# ENGI301Project2.net
KiCad netlist of a schematic drawn in EAGLE
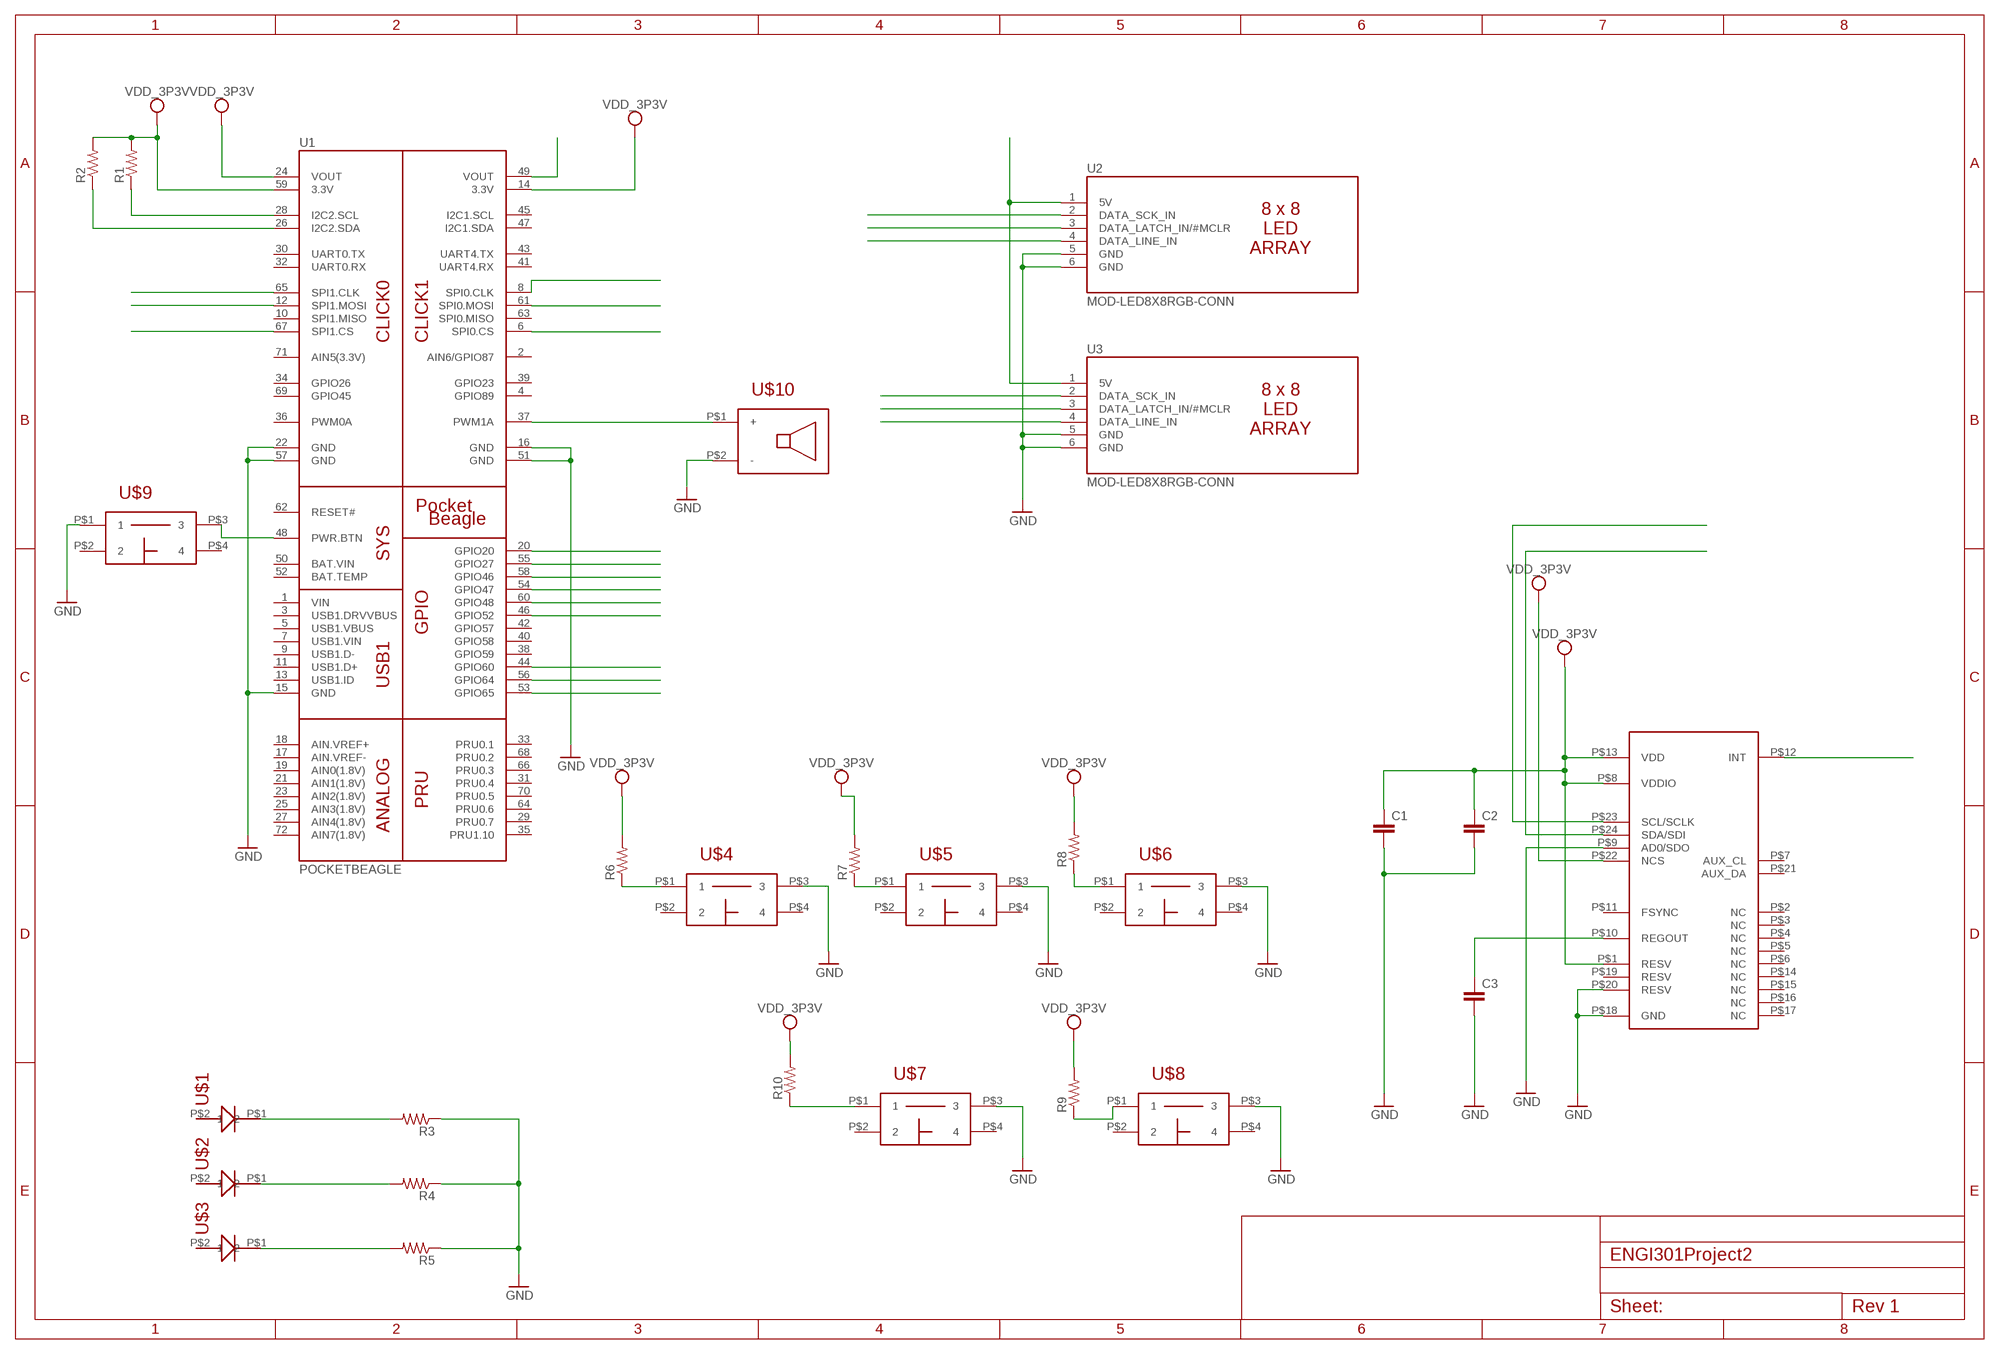
[diagram p0: schematic, sheet 1]

(export (version "E")
  (design (tool "Eeschema 10.0.6"))
  (components
    (comp (ref "C1")
      (value "C_C0603")
      (footprint "eagle-import:C0603")
      (libsource (lib "eagle-import") (part "C_C0603"))
    )
    (comp (ref "C2")
      (value "C_C0603")
      (footprint "eagle-import:C0603")
      (libsource (lib "eagle-import") (part "C_C0603"))
    )
    (comp (ref "C3")
      (value "C_C0603")
      (footprint "eagle-import:C0603")
      (libsource (lib "eagle-import") (part "C_C0603"))
    )
    (comp (ref "R1")
      (value "R_R0603")
      (footprint "eagle-import:R0603")
      (libsource (lib "eagle-import") (part "R_R0603"))
    )
    (comp (ref "R2")
      (value "R_R0603")
      (footprint "eagle-import:R0603")
      (libsource (lib "eagle-import") (part "R_R0603"))
    )
    (comp (ref "R3")
      (value "R_R0603")
      (footprint "eagle-import:R0603")
      (libsource (lib "eagle-import") (part "R_R0603"))
    )
    (comp (ref "R4")
      (value "R_R0603")
      (footprint "eagle-import:R0603")
      (libsource (lib "eagle-import") (part "R_R0603"))
    )
    (comp (ref "R5")
      (value "R_R0603")
      (footprint "eagle-import:R0603")
      (libsource (lib "eagle-import") (part "R_R0603"))
    )
    (comp (ref "R6")
      (value "R_R0603")
      (footprint "eagle-import:R0603")
      (libsource (lib "eagle-import") (part "R_R0603"))
    )
    (comp (ref "R7")
      (value "R_R0603")
      (footprint "eagle-import:R0603")
      (libsource (lib "eagle-import") (part "R_R0603"))
    )
    (comp (ref "R8")
      (value "R_R0603")
      (footprint "eagle-import:R0603")
      (libsource (lib "eagle-import") (part "R_R0603"))
    )
    (comp (ref "R9")
      (value "R_R0603")
      (footprint "eagle-import:R0603")
      (libsource (lib "eagle-import") (part "R_R0603"))
    )
    (comp (ref "R10")
      (value "R_R0603")
      (footprint "eagle-import:R0603")
      (libsource (lib "eagle-import") (part "R_R0603"))
    )
    (comp (ref "U$1")
      (value "LED")
      (footprint "eagle-import:LED")
      (libsource (lib "eagle-import") (part "LED"))
    )
    (comp (ref "U$2")
      (value "LED")
      (footprint "eagle-import:LED")
      (libsource (lib "eagle-import") (part "LED"))
    )
    (comp (ref "U$3")
      (value "LED")
      (footprint "eagle-import:LED")
      (libsource (lib "eagle-import") (part "LED"))
    )
    (comp (ref "U$4")
      (value "BUTTON")
      (footprint "eagle-import:BUTTON")
      (libsource (lib "eagle-import") (part "BUTTON"))
    )
    (comp (ref "U$5")
      (value "BUTTON")
      (footprint "eagle-import:BUTTON")
      (libsource (lib "eagle-import") (part "BUTTON"))
    )
    (comp (ref "U$6")
      (value "BUTTON")
      (footprint "eagle-import:BUTTON")
      (libsource (lib "eagle-import") (part "BUTTON"))
    )
    (comp (ref "U$7")
      (value "BUTTON")
      (footprint "eagle-import:BUTTON")
      (libsource (lib "eagle-import") (part "BUTTON"))
    )
    (comp (ref "U$8")
      (value "BUTTON")
      (footprint "eagle-import:BUTTON")
      (libsource (lib "eagle-import") (part "BUTTON"))
    )
    (comp (ref "U$9")
      (value "BUTTON")
      (footprint "eagle-import:BUTTON")
      (libsource (lib "eagle-import") (part "BUTTON"))
    )
    (comp (ref "U$10")
      (value "BUZZER")
      (footprint "eagle-import:BUZZER")
      (libsource (lib "eagle-import") (part "BUZZER"))
    )
    (comp (ref "U1")
      (value "POCKETBEAGLE")
      (footprint "eagle-import:POCKETBEAGLE")
      (libsource (lib "eagle-import") (part "POCKETBEAGLE"))
    )
    (comp (ref "U2")
      (value "MOD-LED8X8RGB-CONN")
      (footprint "eagle-import:FE06W")
      (libsource (lib "eagle-import") (part "MOD-LED8X8RGB-CONN"))
    )
    (comp (ref "U3")
      (value "MOD-LED8X8RGB-CONN")
      (footprint "eagle-import:FE06W")
      (libsource (lib "eagle-import") (part "MOD-LED8X8RGB-CONN"))
    )
    (comp (ref "U6")
      (value "MPU-9250")
      (footprint "eagle-import:QFN3")
      (libsource (lib "eagle-import") (part "MPU-9250"))
    )
  )
  (nets
    (net (code "1") (name "GND") (class "Default")
      (node (ref "C1") (pin "2") (pinfunction "2_2") (pintype "passive"))
      (node (ref "C2") (pin "2") (pinfunction "2_2") (pintype "passive"))
      (node (ref "C3") (pin "2") (pinfunction "2_2") (pintype "passive"))
      (node (ref "R3") (pin "1") (pinfunction "1_1") (pintype "passive"))
      (node (ref "R4") (pin "1") (pinfunction "1_1") (pintype "passive"))
      (node (ref "R5") (pin "1") (pinfunction "1_1") (pintype "passive"))
      (node (ref "U$10") (pin "P$2") (pinfunction "-_P$2") (pintype "bidirectional"))
      (node (ref "U$4") (pin "P$3") (pinfunction "3_P$3") (pintype "bidirectional"))
      (node (ref "U$5") (pin "P$3") (pinfunction "3_P$3") (pintype "bidirectional"))
      (node (ref "U$6") (pin "P$3") (pinfunction "3_P$3") (pintype "bidirectional"))
      (node (ref "U$7") (pin "P$3") (pinfunction "3_P$3") (pintype "bidirectional"))
      (node (ref "U$8") (pin "P$3") (pinfunction "3_P$3") (pintype "bidirectional"))
      (node (ref "U$9") (pin "P$1") (pinfunction "1_P$1") (pintype "bidirectional"))
      (node (ref "U1") (pin "15") (pinfunction "GND_15") (pintype "bidirectional"))
      (node (ref "U1") (pin "16") (pinfunction "GND_16") (pintype "bidirectional"))
      (node (ref "U1") (pin "22") (pinfunction "GND_22") (pintype "bidirectional"))
      (node (ref "U1") (pin "51") (pinfunction "GND_51") (pintype "bidirectional"))
      (node (ref "U1") (pin "57") (pinfunction "GND_57") (pintype "bidirectional"))
      (node (ref "U2") (pin "5") (pinfunction "GND_5") (pintype "bidirectional"))
      (node (ref "U2") (pin "6") (pinfunction "GND_6") (pintype "bidirectional"))
      (node (ref "U3") (pin "5") (pinfunction "GND_5") (pintype "bidirectional"))
      (node (ref "U3") (pin "6") (pinfunction "GND_6") (pintype "bidirectional"))
      (node (ref "U6") (pin "P$18") (pinfunction "GND_P$18") (pintype "bidirectional"))
      (node (ref "U6") (pin "P$20") (pinfunction "RESV_P$20") (pintype "bidirectional"))
      (node (ref "U6") (pin "P$9") (pinfunction "AD0/SDO_P$9") (pintype "bidirectional"))
    )
    (net (code "2") (name "Net-(U$1-1)") (class "Default")
      (node (ref "R3") (pin "2") (pinfunction "2_2") (pintype "passive"))
      (node (ref "U$1") (pin "P$1") (pinfunction "1_P$1") (pintype "bidirectional"))
    )
    (net (code "3") (name "Net-(U$2-1)") (class "Default")
      (node (ref "R4") (pin "2") (pinfunction "2_2") (pintype "passive"))
      (node (ref "U$2") (pin "P$1") (pinfunction "1_P$1") (pintype "bidirectional"))
    )
    (net (code "4") (name "Net-(U$3-1)") (class "Default")
      (node (ref "R5") (pin "2") (pinfunction "2_2") (pintype "passive"))
      (node (ref "U$3") (pin "P$1") (pinfunction "1_P$1") (pintype "bidirectional"))
    )
    (net (code "5") (name "Net-(U$4-1)") (class "Default")
      (node (ref "R6") (pin "1") (pinfunction "1_1") (pintype "passive"))
      (node (ref "U$4") (pin "P$1") (pinfunction "1_P$1") (pintype "bidirectional"))
    )
    (net (code "6") (name "Net-(U$5-1)") (class "Default")
      (node (ref "R7") (pin "1") (pinfunction "1_1") (pintype "passive"))
      (node (ref "U$5") (pin "P$1") (pinfunction "1_P$1") (pintype "bidirectional"))
    )
    (net (code "7") (name "Net-(U$6-1)") (class "Default")
      (node (ref "R8") (pin "1") (pinfunction "1_1") (pintype "passive"))
      (node (ref "U$6") (pin "P$1") (pinfunction "1_P$1") (pintype "bidirectional"))
    )
    (net (code "8") (name "Net-(U$7-1)") (class "Default")
      (node (ref "R10") (pin "1") (pinfunction "1_1") (pintype "passive"))
      (node (ref "U$7") (pin "P$1") (pinfunction "1_P$1") (pintype "bidirectional"))
    )
    (net (code "9") (name "Net-(U$8-1)") (class "Default")
      (node (ref "R9") (pin "1") (pinfunction "1_1") (pintype "passive"))
      (node (ref "U$8") (pin "P$1") (pinfunction "1_P$1") (pintype "bidirectional"))
    )
    (net (code "10") (name "Net-(U$9-3)") (class "Default")
      (node (ref "U$9") (pin "P$3") (pinfunction "3_P$3") (pintype "bidirectional"))
      (node (ref "U1") (pin "48") (pinfunction "PWR.BTN_48") (pintype "bidirectional"))
    )
    (net (code "11") (name "Net-(U$10-+)") (class "Default")
      (node (ref "U$10") (pin "P$1") (pinfunction "+_P$1") (pintype "bidirectional"))
      (node (ref "U1") (pin "37") (pinfunction "PWM1A_37") (pintype "bidirectional"))
    )
    (net (code "12") (name "Net-(U1-I2C2.SCL)") (class "Default")
      (node (ref "R1") (pin "1") (pinfunction "1_1") (pintype "passive"))
      (node (ref "U1") (pin "28") (pinfunction "I2C2.SCL_28") (pintype "bidirectional"))
    )
    (net (code "13") (name "Net-(U1-I2C2.SDA)") (class "Default")
      (node (ref "R2") (pin "1") (pinfunction "1_1") (pintype "passive"))
      (node (ref "U1") (pin "26") (pinfunction "I2C2.SDA_26") (pintype "bidirectional"))
    )
    (net (code "14") (name "Net-(U2-5V)") (class "Default")
      (node (ref "U2") (pin "1") (pinfunction "5V_1") (pintype "bidirectional"))
      (node (ref "U3") (pin "1") (pinfunction "5V_1") (pintype "bidirectional"))
    )
    (net (code "15") (name "Net-(U6-REGOUT)") (class "Default")
      (node (ref "C3") (pin "1") (pinfunction "1_1") (pintype "passive"))
      (node (ref "U6") (pin "P$10") (pinfunction "REGOUT_P$10") (pintype "bidirectional"))
    )
    (net (code "16") (name "VDD_3P3V") (class "Default")
      (node (ref "C1") (pin "1") (pinfunction "1_1") (pintype "passive"))
      (node (ref "C2") (pin "1") (pinfunction "1_1") (pintype "passive"))
      (node (ref "R1") (pin "2") (pinfunction "2_2") (pintype "passive"))
      (node (ref "R10") (pin "2") (pinfunction "2_2") (pintype "passive"))
      (node (ref "R2") (pin "2") (pinfunction "2_2") (pintype "passive"))
      (node (ref "R6") (pin "2") (pinfunction "2_2") (pintype "passive"))
      (node (ref "R7") (pin "2") (pinfunction "2_2") (pintype "passive"))
      (node (ref "R8") (pin "2") (pinfunction "2_2") (pintype "passive"))
      (node (ref "R9") (pin "2") (pinfunction "2_2") (pintype "passive"))
      (node (ref "U1") (pin "14") (pinfunction "3.3V_14") (pintype "bidirectional"))
      (node (ref "U1") (pin "24") (pinfunction "VOUT_24") (pintype "bidirectional"))
      (node (ref "U1") (pin "59") (pinfunction "3.3V_59") (pintype "bidirectional"))
      (node (ref "U6") (pin "P$1") (pinfunction "RESV_P$1") (pintype "bidirectional"))
      (node (ref "U6") (pin "P$13") (pinfunction "VDD_P$13") (pintype "bidirectional"))
      (node (ref "U6") (pin "P$22") (pinfunction "NCS_P$22") (pintype "bidirectional"))
      (node (ref "U6") (pin "P$8") (pinfunction "VDDIO_P$8") (pintype "bidirectional"))
    )
    (net (code "17") (name "unconnected-(U$1-2-PadP$2)") (class "Default")
      (node (ref "U$1") (pin "P$2") (pinfunction "2_P$2") (pintype "bidirectional"))
    )
    (net (code "18") (name "unconnected-(U$2-2-PadP$2)") (class "Default")
      (node (ref "U$2") (pin "P$2") (pinfunction "2_P$2") (pintype "bidirectional"))
    )
    (net (code "19") (name "unconnected-(U$3-2-PadP$2)") (class "Default")
      (node (ref "U$3") (pin "P$2") (pinfunction "2_P$2") (pintype "bidirectional"))
    )
    (net (code "20") (name "unconnected-(U$4-2-PadP$2)") (class "Default")
      (node (ref "U$4") (pin "P$2") (pinfunction "2_P$2") (pintype "bidirectional"))
    )
    (net (code "21") (name "unconnected-(U$4-4-PadP$4)") (class "Default")
      (node (ref "U$4") (pin "P$4") (pinfunction "4_P$4") (pintype "bidirectional"))
    )
    (net (code "22") (name "unconnected-(U$5-2-PadP$2)") (class "Default")
      (node (ref "U$5") (pin "P$2") (pinfunction "2_P$2") (pintype "bidirectional"))
    )
    (net (code "23") (name "unconnected-(U$5-4-PadP$4)") (class "Default")
      (node (ref "U$5") (pin "P$4") (pinfunction "4_P$4") (pintype "bidirectional"))
    )
    (net (code "24") (name "unconnected-(U$6-2-PadP$2)") (class "Default")
      (node (ref "U$6") (pin "P$2") (pinfunction "2_P$2") (pintype "bidirectional"))
    )
    (net (code "25") (name "unconnected-(U$6-4-PadP$4)") (class "Default")
      (node (ref "U$6") (pin "P$4") (pinfunction "4_P$4") (pintype "bidirectional"))
    )
    (net (code "26") (name "unconnected-(U$7-2-PadP$2)") (class "Default")
      (node (ref "U$7") (pin "P$2") (pinfunction "2_P$2") (pintype "bidirectional"))
    )
    (net (code "27") (name "unconnected-(U$7-4-PadP$4)") (class "Default")
      (node (ref "U$7") (pin "P$4") (pinfunction "4_P$4") (pintype "bidirectional"))
    )
    (net (code "28") (name "unconnected-(U$8-2-PadP$2)") (class "Default")
      (node (ref "U$8") (pin "P$2") (pinfunction "2_P$2") (pintype "bidirectional"))
    )
    (net (code "29") (name "unconnected-(U$8-4-PadP$4)") (class "Default")
      (node (ref "U$8") (pin "P$4") (pinfunction "4_P$4") (pintype "bidirectional"))
    )
    (net (code "30") (name "unconnected-(U$9-2-PadP$2)") (class "Default")
      (node (ref "U$9") (pin "P$2") (pinfunction "2_P$2") (pintype "bidirectional"))
    )
    (net (code "31") (name "unconnected-(U$9-4-PadP$4)") (class "Default")
      (node (ref "U$9") (pin "P$4") (pinfunction "4_P$4") (pintype "bidirectional"))
    )
    (net (code "32") (name "unconnected-(U1-AIN.VREF+-Pad18)") (class "Default")
      (node (ref "U1") (pin "18") (pinfunction "AIN.VREF+_18") (pintype "bidirectional"))
    )
    (net (code "33") (name "unconnected-(U1-AIN.VREF--Pad17)") (class "Default")
      (node (ref "U1") (pin "17") (pinfunction "AIN.VREF-_17") (pintype "bidirectional"))
    )
    (net (code "34") (name "unconnected-(U1-AIN0(1.8V)-Pad19)") (class "Default")
      (node (ref "U1") (pin "19") (pinfunction "AIN0(1.8V)_19") (pintype "bidirectional"))
    )
    (net (code "35") (name "unconnected-(U1-AIN1(1.8V)-Pad21)") (class "Default")
      (node (ref "U1") (pin "21") (pinfunction "AIN1(1.8V)_21") (pintype "bidirectional"))
    )
    (net (code "36") (name "unconnected-(U1-AIN2(1.8V)-Pad23)") (class "Default")
      (node (ref "U1") (pin "23") (pinfunction "AIN2(1.8V)_23") (pintype "bidirectional"))
    )
    (net (code "37") (name "unconnected-(U1-AIN3(1.8V)-Pad25)") (class "Default")
      (node (ref "U1") (pin "25") (pinfunction "AIN3(1.8V)_25") (pintype "bidirectional"))
    )
    (net (code "38") (name "unconnected-(U1-AIN4(1.8V)-Pad27)") (class "Default")
      (node (ref "U1") (pin "27") (pinfunction "AIN4(1.8V)_27") (pintype "bidirectional"))
    )
    (net (code "39") (name "unconnected-(U1-AIN5(3.3V)-Pad71)") (class "Default")
      (node (ref "U1") (pin "71") (pinfunction "AIN5(3.3V)_71") (pintype "bidirectional"))
    )
    (net (code "40") (name "unconnected-(U1-AIN6{slash}GPIO87-Pad2)") (class "Default")
      (node (ref "U1") (pin "2") (pinfunction "AIN6/GPIO87_2") (pintype "bidirectional"))
    )
    (net (code "41") (name "unconnected-(U1-AIN7(1.8V)-Pad72)") (class "Default")
      (node (ref "U1") (pin "72") (pinfunction "AIN7(1.8V)_72") (pintype "bidirectional"))
    )
    (net (code "42") (name "unconnected-(U1-BAT.TEMP-Pad52)") (class "Default")
      (node (ref "U1") (pin "52") (pinfunction "BAT.TEMP_52") (pintype "bidirectional"))
    )
    (net (code "43") (name "unconnected-(U1-BAT.VIN-Pad50)") (class "Default")
      (node (ref "U1") (pin "50") (pinfunction "BAT.VIN_50") (pintype "bidirectional"))
    )
    (net (code "44") (name "unconnected-(U1-GPIO20-Pad20)") (class "Default")
      (node (ref "U1") (pin "20") (pinfunction "GPIO20_20") (pintype "bidirectional"))
    )
    (net (code "45") (name "unconnected-(U1-GPIO23-Pad39)") (class "Default")
      (node (ref "U1") (pin "39") (pinfunction "GPIO23_39") (pintype "bidirectional"))
    )
    (net (code "46") (name "unconnected-(U1-GPIO26-Pad34)") (class "Default")
      (node (ref "U1") (pin "34") (pinfunction "GPIO26_34") (pintype "bidirectional"))
    )
    (net (code "47") (name "unconnected-(U1-GPIO27-Pad55)") (class "Default")
      (node (ref "U1") (pin "55") (pinfunction "GPIO27_55") (pintype "bidirectional"))
    )
    (net (code "48") (name "unconnected-(U1-GPIO45-Pad69)") (class "Default")
      (node (ref "U1") (pin "69") (pinfunction "GPIO45_69") (pintype "bidirectional"))
    )
    (net (code "49") (name "unconnected-(U1-GPIO46-Pad58)") (class "Default")
      (node (ref "U1") (pin "58") (pinfunction "GPIO46_58") (pintype "bidirectional"))
    )
    (net (code "50") (name "unconnected-(U1-GPIO47-Pad54)") (class "Default")
      (node (ref "U1") (pin "54") (pinfunction "GPIO47_54") (pintype "bidirectional"))
    )
    (net (code "51") (name "unconnected-(U1-GPIO48-Pad60)") (class "Default")
      (node (ref "U1") (pin "60") (pinfunction "GPIO48_60") (pintype "bidirectional"))
    )
    (net (code "52") (name "unconnected-(U1-GPIO52-Pad46)") (class "Default")
      (node (ref "U1") (pin "46") (pinfunction "GPIO52_46") (pintype "bidirectional"))
    )
    (net (code "53") (name "unconnected-(U1-GPIO57-Pad42)") (class "Default")
      (node (ref "U1") (pin "42") (pinfunction "GPIO57_42") (pintype "bidirectional"))
    )
    (net (code "54") (name "unconnected-(U1-GPIO58-Pad40)") (class "Default")
      (node (ref "U1") (pin "40") (pinfunction "GPIO58_40") (pintype "bidirectional"))
    )
    (net (code "55") (name "unconnected-(U1-GPIO59-Pad38)") (class "Default")
      (node (ref "U1") (pin "38") (pinfunction "GPIO59_38") (pintype "bidirectional"))
    )
    (net (code "56") (name "unconnected-(U1-GPIO60-Pad44)") (class "Default")
      (node (ref "U1") (pin "44") (pinfunction "GPIO60_44") (pintype "bidirectional"))
    )
    (net (code "57") (name "unconnected-(U1-GPIO64-Pad56)") (class "Default")
      (node (ref "U1") (pin "56") (pinfunction "GPIO64_56") (pintype "bidirectional"))
    )
    (net (code "58") (name "unconnected-(U1-GPIO65-Pad53)") (class "Default")
      (node (ref "U1") (pin "53") (pinfunction "GPIO65_53") (pintype "bidirectional"))
    )
    (net (code "59") (name "unconnected-(U1-GPIO89-Pad4)") (class "Default")
      (node (ref "U1") (pin "4") (pinfunction "GPIO89_4") (pintype "bidirectional"))
    )
    (net (code "60") (name "unconnected-(U1-I2C1.SCL-Pad45)") (class "Default")
      (node (ref "U1") (pin "45") (pinfunction "I2C1.SCL_45") (pintype "bidirectional"))
    )
    (net (code "61") (name "unconnected-(U1-I2C1.SDA-Pad47)") (class "Default")
      (node (ref "U1") (pin "47") (pinfunction "I2C1.SDA_47") (pintype "bidirectional"))
    )
    (net (code "62") (name "unconnected-(U1-PRU0.1-Pad33)") (class "Default")
      (node (ref "U1") (pin "33") (pinfunction "PRU0.1_33") (pintype "bidirectional"))
    )
    (net (code "63") (name "unconnected-(U1-PRU0.2-Pad68)") (class "Default")
      (node (ref "U1") (pin "68") (pinfunction "PRU0.2_68") (pintype "bidirectional"))
    )
    (net (code "64") (name "unconnected-(U1-PRU0.3-Pad66)") (class "Default")
      (node (ref "U1") (pin "66") (pinfunction "PRU0.3_66") (pintype "bidirectional"))
    )
    (net (code "65") (name "unconnected-(U1-PRU0.4-Pad31)") (class "Default")
      (node (ref "U1") (pin "31") (pinfunction "PRU0.4_31") (pintype "bidirectional"))
    )
    (net (code "66") (name "unconnected-(U1-PRU0.5-Pad70)") (class "Default")
      (node (ref "U1") (pin "70") (pinfunction "PRU0.5_70") (pintype "bidirectional"))
    )
    (net (code "67") (name "unconnected-(U1-PRU0.6-Pad64)") (class "Default")
      (node (ref "U1") (pin "64") (pinfunction "PRU0.6_64") (pintype "bidirectional"))
    )
    (net (code "68") (name "unconnected-(U1-PRU0.7-Pad29)") (class "Default")
      (node (ref "U1") (pin "29") (pinfunction "PRU0.7_29") (pintype "bidirectional"))
    )
    (net (code "69") (name "unconnected-(U1-PRU1.10-Pad35)") (class "Default")
      (node (ref "U1") (pin "35") (pinfunction "PRU1.10_35") (pintype "bidirectional"))
    )
    (net (code "70") (name "unconnected-(U1-PWM0A-Pad36)") (class "Default")
      (node (ref "U1") (pin "36") (pinfunction "PWM0A_36") (pintype "bidirectional"))
    )
    (net (code "71") (name "unconnected-(U1-RESET#-Pad62)") (class "Default")
      (node (ref "U1") (pin "62") (pinfunction "RESET#_62") (pintype "bidirectional"))
    )
    (net (code "72") (name "unconnected-(U1-SPI0.CLK-Pad8)") (class "Default")
      (node (ref "U1") (pin "8") (pinfunction "SPI0.CLK_8") (pintype "bidirectional"))
    )
    (net (code "73") (name "unconnected-(U1-SPI0.CS-Pad6)") (class "Default")
      (node (ref "U1") (pin "6") (pinfunction "SPI0.CS_6") (pintype "bidirectional"))
    )
    (net (code "74") (name "unconnected-(U1-SPI0.MISO-Pad63)") (class "Default")
      (node (ref "U1") (pin "63") (pinfunction "SPI0.MISO_63") (pintype "bidirectional"))
    )
    (net (code "75") (name "unconnected-(U1-SPI0.MOSI-Pad61)") (class "Default")
      (node (ref "U1") (pin "61") (pinfunction "SPI0.MOSI_61") (pintype "bidirectional"))
    )
    (net (code "76") (name "unconnected-(U1-SPI1.CLK-Pad65)") (class "Default")
      (node (ref "U1") (pin "65") (pinfunction "SPI1.CLK_65") (pintype "bidirectional"))
    )
    (net (code "77") (name "unconnected-(U1-SPI1.CS-Pad67)") (class "Default")
      (node (ref "U1") (pin "67") (pinfunction "SPI1.CS_67") (pintype "bidirectional"))
    )
    (net (code "78") (name "unconnected-(U1-SPI1.MISO-Pad10)") (class "Default")
      (node (ref "U1") (pin "10") (pinfunction "SPI1.MISO_10") (pintype "bidirectional"))
    )
    (net (code "79") (name "unconnected-(U1-SPI1.MOSI-Pad12)") (class "Default")
      (node (ref "U1") (pin "12") (pinfunction "SPI1.MOSI_12") (pintype "bidirectional"))
    )
    (net (code "80") (name "unconnected-(U1-UART0.RX-Pad32)") (class "Default")
      (node (ref "U1") (pin "32") (pinfunction "UART0.RX_32") (pintype "bidirectional"))
    )
    (net (code "81") (name "unconnected-(U1-UART0.TX-Pad30)") (class "Default")
      (node (ref "U1") (pin "30") (pinfunction "UART0.TX_30") (pintype "bidirectional"))
    )
    (net (code "82") (name "unconnected-(U1-UART4.RX-Pad41)") (class "Default")
      (node (ref "U1") (pin "41") (pinfunction "UART4.RX_41") (pintype "bidirectional"))
    )
    (net (code "83") (name "unconnected-(U1-UART4.TX-Pad43)") (class "Default")
      (node (ref "U1") (pin "43") (pinfunction "UART4.TX_43") (pintype "bidirectional"))
    )
    (net (code "84") (name "unconnected-(U1-USB1.D+-Pad11)") (class "Default")
      (node (ref "U1") (pin "11") (pinfunction "USB1.D+_11") (pintype "bidirectional"))
    )
    (net (code "85") (name "unconnected-(U1-USB1.D--Pad9)") (class "Default")
      (node (ref "U1") (pin "9") (pinfunction "USB1.D-_9") (pintype "bidirectional"))
    )
    (net (code "86") (name "unconnected-(U1-USB1.DRVVBUS-Pad3)") (class "Default")
      (node (ref "U1") (pin "3") (pinfunction "USB1.DRVVBUS_3") (pintype "bidirectional"))
    )
    (net (code "87") (name "unconnected-(U1-USB1.ID-Pad13)") (class "Default")
      (node (ref "U1") (pin "13") (pinfunction "USB1.ID_13") (pintype "bidirectional"))
    )
    (net (code "88") (name "unconnected-(U1-USB1.VBUS-Pad5)") (class "Default")
      (node (ref "U1") (pin "5") (pinfunction "USB1.VBUS_5") (pintype "bidirectional"))
    )
    (net (code "89") (name "unconnected-(U1-USB1.VIN-Pad7)") (class "Default")
      (node (ref "U1") (pin "7") (pinfunction "USB1.VIN_7") (pintype "bidirectional"))
    )
    (net (code "90") (name "unconnected-(U1-VIN-Pad1)") (class "Default")
      (node (ref "U1") (pin "1") (pinfunction "VIN_1") (pintype "bidirectional"))
    )
    (net (code "91") (name "unconnected-(U1-VOUT-Pad49)") (class "Default")
      (node (ref "U1") (pin "49") (pinfunction "VOUT_49") (pintype "bidirectional"))
    )
    (net (code "92") (name "unconnected-(U2-DATA_LATCH_IN{slash}#MCLR-Pad3)") (class "Default")
      (node (ref "U2") (pin "3") (pinfunction "DATA_LATCH_IN/#MCLR_3") (pintype "bidirectional"))
    )
    (net (code "93") (name "unconnected-(U2-DATA_LINE_IN-Pad4)") (class "Default")
      (node (ref "U2") (pin "4") (pinfunction "DATA_LINE_IN_4") (pintype "bidirectional"))
    )
    (net (code "94") (name "unconnected-(U2-DATA_SCK_IN-Pad2)") (class "Default")
      (node (ref "U2") (pin "2") (pinfunction "DATA_SCK_IN_2") (pintype "bidirectional"))
    )
    (net (code "95") (name "unconnected-(U3-DATA_LATCH_IN{slash}#MCLR-Pad3)") (class "Default")
      (node (ref "U3") (pin "3") (pinfunction "DATA_LATCH_IN/#MCLR_3") (pintype "bidirectional"))
    )
    (net (code "96") (name "unconnected-(U3-DATA_LINE_IN-Pad4)") (class "Default")
      (node (ref "U3") (pin "4") (pinfunction "DATA_LINE_IN_4") (pintype "bidirectional"))
    )
    (net (code "97") (name "unconnected-(U3-DATA_SCK_IN-Pad2)") (class "Default")
      (node (ref "U3") (pin "2") (pinfunction "DATA_SCK_IN_2") (pintype "bidirectional"))
    )
    (net (code "98") (name "unconnected-(U6-AUX_CL-PadP$7)") (class "Default")
      (node (ref "U6") (pin "P$7") (pinfunction "AUX_CL_P$7") (pintype "bidirectional"))
    )
    (net (code "99") (name "unconnected-(U6-AUX_DA-PadP$21)") (class "Default")
      (node (ref "U6") (pin "P$21") (pinfunction "AUX_DA_P$21") (pintype "bidirectional"))
    )
    (net (code "100") (name "unconnected-(U6-FSYNC-PadP$11)") (class "Default")
      (node (ref "U6") (pin "P$11") (pinfunction "FSYNC_P$11") (pintype "bidirectional"))
    )
    (net (code "101") (name "unconnected-(U6-INT-PadP$12)") (class "Default")
      (node (ref "U6") (pin "P$12") (pinfunction "INT_P$12") (pintype "bidirectional"))
    )
    (net (code "102") (name "unconnected-(U6-NC-PadP$2)") (class "Default")
      (node (ref "U6") (pin "P$2") (pinfunction "NC_P$2") (pintype "bidirectional"))
    )
    (net (code "103") (name "unconnected-(U6-NC-PadP$3)") (class "Default")
      (node (ref "U6") (pin "P$3") (pinfunction "NC_P$3") (pintype "bidirectional"))
    )
    (net (code "104") (name "unconnected-(U6-NC-PadP$4)") (class "Default")
      (node (ref "U6") (pin "P$4") (pinfunction "NC_P$4") (pintype "bidirectional"))
    )
    (net (code "105") (name "unconnected-(U6-NC-PadP$5)") (class "Default")
      (node (ref "U6") (pin "P$5") (pinfunction "NC_P$5") (pintype "bidirectional"))
    )
    (net (code "106") (name "unconnected-(U6-NC-PadP$6)") (class "Default")
      (node (ref "U6") (pin "P$6") (pinfunction "NC_P$6") (pintype "bidirectional"))
    )
    (net (code "107") (name "unconnected-(U6-NC-PadP$14)") (class "Default")
      (node (ref "U6") (pin "P$14") (pinfunction "NC_P$14") (pintype "bidirectional"))
    )
    (net (code "108") (name "unconnected-(U6-NC-PadP$15)") (class "Default")
      (node (ref "U6") (pin "P$15") (pinfunction "NC_P$15") (pintype "bidirectional"))
    )
    (net (code "109") (name "unconnected-(U6-NC-PadP$16)") (class "Default")
      (node (ref "U6") (pin "P$16") (pinfunction "NC_P$16") (pintype "bidirectional"))
    )
    (net (code "110") (name "unconnected-(U6-NC-PadP$17)") (class "Default")
      (node (ref "U6") (pin "P$17") (pinfunction "NC_P$17") (pintype "bidirectional"))
    )
    (net (code "111") (name "unconnected-(U6-RESV-PadP$19)") (class "Default")
      (node (ref "U6") (pin "P$19") (pinfunction "RESV_P$19") (pintype "bidirectional"))
    )
    (net (code "112") (name "unconnected-(U6-SCL{slash}SCLK-PadP$23)") (class "Default")
      (node (ref "U6") (pin "P$23") (pinfunction "SCL/SCLK_P$23") (pintype "bidirectional"))
    )
    (net (code "113") (name "unconnected-(U6-SDA{slash}SDI-PadP$24)") (class "Default")
      (node (ref "U6") (pin "P$24") (pinfunction "SDA/SDI_P$24") (pintype "bidirectional"))
    )
  )
)
